# 03_MCU.net
KiCad netlist of a schematic drawn in Altium Designer
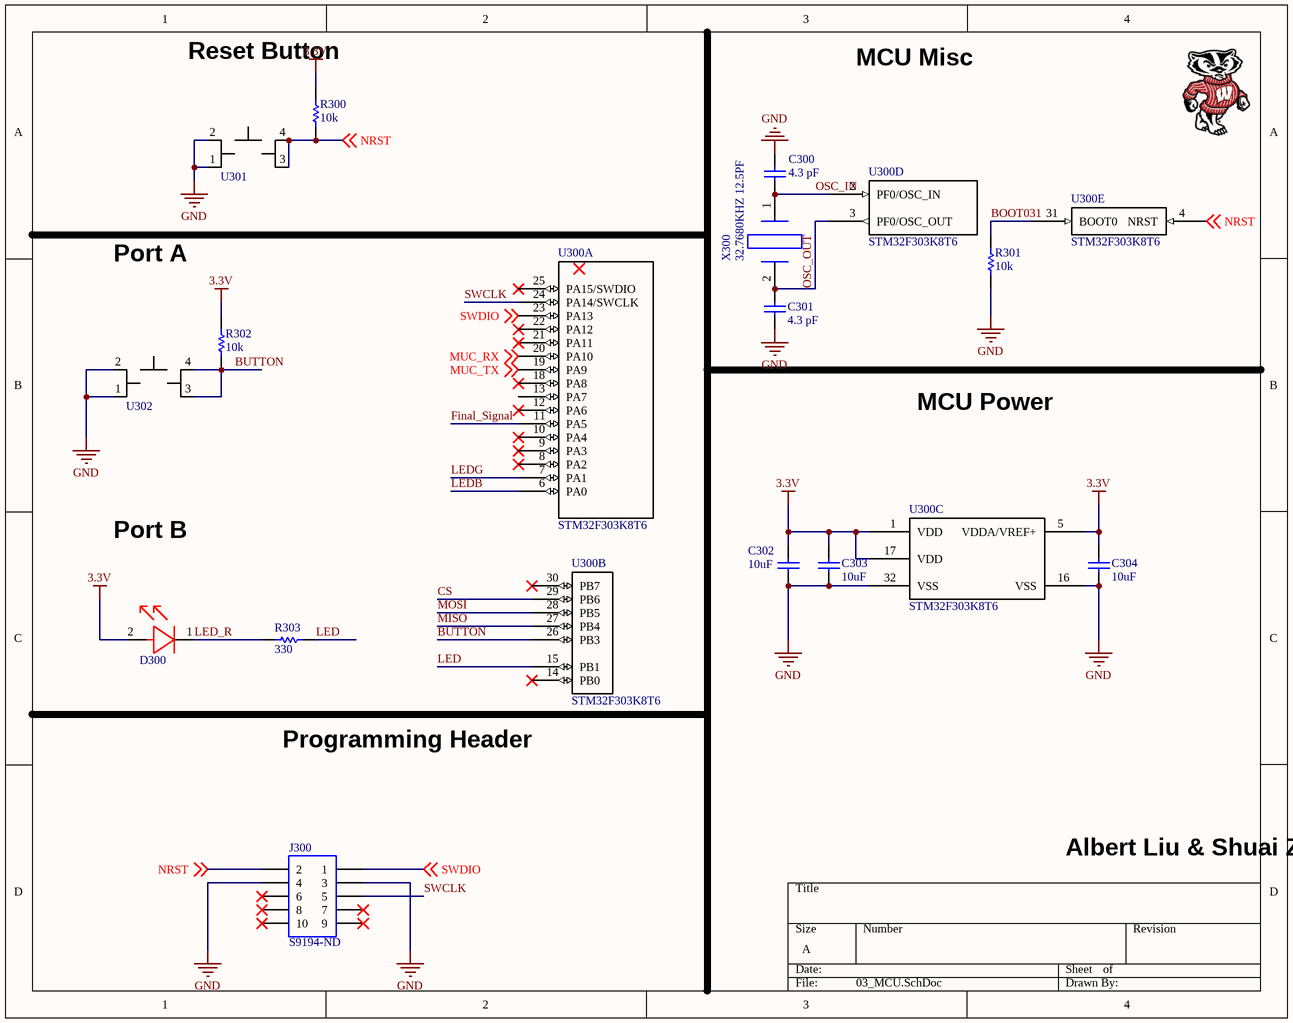
[diagram p0: 03_MCU.SchDoc]

(export (version "E")
  (design (tool "Eeschema 10.0.6"))
  (components
    (comp (ref "C300")
      (value "CAP_0805_P_004.30")
      (footprint "CAP_0805")
      (description "CAP CER 4.3PF 100V NP0 0805")
      (fields
        (field (name "MANUFACTURER") "Kyocera AVX")
        (field (name "MANUFACTURER PART NUMBER") "08051A4R3CAT2A")
        (field (name "CAPACITANCE VALUE") "4.3 pF")
      )
      (libsource (lib "ece315-S20") (part "CAP_0805_P_004.30"))
    )
    (comp (ref "C301")
      (value "CAP_0805_P_004.30")
      (footprint "CAP_0805")
      (description "CAP CER 4.3PF 100V NP0 0805")
      (fields
        (field (name "MANUFACTURER") "Kyocera AVX")
        (field (name "MANUFACTURER PART NUMBER") "08051A4R3CAT2A")
        (field (name "CAPACITANCE VALUE") "4.3 pF")
      )
      (libsource (lib "ece315-S20") (part "CAP_0805_P_004.30"))
    )
    (comp (ref "C302")
      (value "10uF")
      (footprint "CAP_0805")
      (description "CAP CER 10UF 16V X7R 0805")
      (fields
        (field (name "MANUFACTURER") "Samsung")
        (field (name "MANUFACTURER PART NUMBER") "CL21A106KPCLQNC")
        (field (name "CAPACITANCE") "10uF")
      )
      (libsource (lib "ece315-S20") (part "CAP_0805_U_010.00"))
    )
    (comp (ref "C303")
      (value "10uF")
      (footprint "CAP_0805")
      (description "CAP CER 10UF 16V X7R 0805")
      (fields
        (field (name "MANUFACTURER") "Samsung")
        (field (name "MANUFACTURER PART NUMBER") "CL21A106KPCLQNC")
        (field (name "CAPACITANCE") "10uF")
      )
      (libsource (lib "ece315-S20") (part "CAP_0805_U_010.00"))
    )
    (comp (ref "C304")
      (value "10uF")
      (footprint "CAP_0805")
      (description "CAP CER 10UF 16V X7R 0805")
      (fields
        (field (name "MANUFACTURER") "Samsung")
        (field (name "MANUFACTURER PART NUMBER") "CL21A106KPCLQNC")
        (field (name "CAPACITANCE") "10uF")
      )
      (libsource (lib "ece315-S20") (part "CAP_0805_U_010.00"))
    )
    (comp (ref "D300")
      (value "LED_RED_0805.1")
      (footprint "LED_RED_0805")
      (description "LED SUPER RED CLR THIN 0805 SMD")
      (fields
        (field (name "MANUFACTURER") "Vishay / Lite-On")
        (field (name "MANUFACTURER PART NUMBER") "LTST-C171KRKT")
      )
      (libsource (lib "ece315-S20") (part "LED_RED_0805.1"))
    )
    (comp (ref "J300")
      (value "SFH11-PBPC-D05-ST-BK")
      (footprint "SFH11-PBPC-D05-ST-BK")
      (description "CONN HDR 10POS 0.1 GOLD PCB")
      (fields (field (name "SUPPLIER PART NUMBER 1") "S9194-ND"))
      (libsource (lib "ece315-S20") (part "SFH11-PBPC-D05-ST-BK"))
    )
    (comp (ref "R300")
      (value "10K")
      (footprint "RES_0805")
      (description "RES SMD 10K OHM 1% 1/8W 0805")
      (fields
        (field (name "MANUFACTURER") "Panasonic / Panasonic ECG")
        (field (name "MANUFACTURER PART NUMBER") "ERJ-6ENF1002V")
        (field (name "RESISTANCE") "10k")
      )
      (libsource (lib "ece315-S20") (part "RES_0805_K_010.00"))
    )
    (comp (ref "R301")
      (value "10K")
      (footprint "RES_0805")
      (description "RES SMD 10K OHM 1% 1/8W 0805")
      (fields
        (field (name "MANUFACTURER") "Panasonic / Panasonic ECG")
        (field (name "MANUFACTURER PART NUMBER") "ERJ-6ENF1002V")
        (field (name "RESISTANCE") "10k")
      )
      (libsource (lib "ece315-S20") (part "RES_0805_K_010.00"))
    )
    (comp (ref "R302")
      (value "10K")
      (footprint "RES_0805")
      (description "RES SMD 10K OHM 1% 1/8W 0805")
      (fields
        (field (name "MANUFACTURER") "Panasonic / Panasonic ECG")
        (field (name "MANUFACTURER PART NUMBER") "ERJ-6ENF1002V")
        (field (name "RESISTANCE") "10k")
      )
      (libsource (lib "ece315-S20") (part "RES_0805_K_010.00"))
    )
    (comp (ref "R303")
      (value "330")
      (footprint "RES_0805")
      (description "RES SMD 330 OHM 1% 1/8W 0805")
      (fields
        (field (name "MANUFACTURER") "Panasonic / Panasonic ECG")
        (field (name "MANUFACTURER PART NUMBER") "ERJ-6ENF3300V")
        (field (name "RESISTANCE") "330")
      )
      (libsource (lib "ece315-S20") (part "RES_0805_R_330.00"))
    )
    (comp (ref "U300")
      (value "IC_STM32F303K8T6")
      (footprint "LQFP32")
      (description "ARM® Cortex®-M4 STM32 F3 Microcontroller IC 32-Bit 72MHz 64KB (64K x 8) FLASH 32-LQFP (7x7)")
      (fields
        (field (name "MANUFACTURER") "STMicroelectronics")
        (field (name "MANUFACTURER PART NUMBER") "STM32F303K8T6")
      )
      (libsource (lib "ece315-S20") (part "IC_STM32F303K8T6"))
    )
    (comp (ref "U301")
      (value "SWITCH_6mm_6mm_smd")
      (footprint "SWITCH_6mm_6mm_smd")
      (description "SWITCH TACTILE SPST-NO 0.05A 12V")
      (fields
        (field (name "MANUFACTURER") "C&K Components")
        (field (name "MANUFACTURER PART NUMBER") "PTS645SH50SMTR92 LFS")
      )
      (libsource (lib "ece315-S20") (part "SWITCH_6mm_6mm_smd"))
    )
    (comp (ref "U302")
      (value "SWITCH_6mm_6mm_smd")
      (footprint "SWITCH_6mm_6mm_smd")
      (description "SWITCH TACTILE SPST-NO 0.05A 12V")
      (fields
        (field (name "MANUFACTURER") "C&K Components")
        (field (name "MANUFACTURER PART NUMBER") "PTS645SH50SMTR92 LFS")
      )
      (libsource (lib "ece315-S20") (part "SWITCH_6mm_6mm_smd"))
    )
    (comp (ref "X300")
      (value "32.7680KHZ 12.5PF")
      (footprint "NX3215SA-32.768K-STD-MUA-8")
      (description "CRYSTAL 32.768KHZ 12.5PF SMD")
      (fields
        (field (name "MANUFACTURER") "Nihon Dempa Kogyo (NDK)")
        (field (name "MANUFACTURER PART NUMBER") "NX3215SA-32.768K-STD-MUA-8")
      )
      (libsource (lib "ece315-S20") (part "CRYSTAL_NX3215SA-32.768K"))
    )
  )
  (nets
    (net (code "1") (name "/BOOT031") (class "Default")
      (node (ref "R301") (pin "2") (pinfunction "2_2") (pintype "passive"))
      (node (ref "U300") (pin "31") (pinfunction "BOOT0_31") (pintype "input"))
    )
    (net (code "2") (name "/BUTTON") (class "Default")
      (node (ref "R302") (pin "1") (pinfunction "1_1") (pintype "passive"))
      (node (ref "U300") (pin "26") (pinfunction "PB3_26") (pintype "bidirectional"))
      (node (ref "U302") (pin "3") (pinfunction "3_3") (pintype "passive"))
      (node (ref "U302") (pin "4") (pinfunction "VCCIO_4") (pintype "passive"))
    )
    (net (code "3") (name "/CS") (class "Default")
      (node (ref "U300") (pin "29") (pinfunction "PB6_29") (pintype "bidirectional"))
    )
    (net (code "4") (name "/Final_Signal") (class "Default")
      (node (ref "U300") (pin "11") (pinfunction "PA5_11") (pintype "bidirectional"))
    )
    (net (code "5") (name "/LED") (class "Default")
      (node (ref "R303") (pin "2") (pinfunction "2_2") (pintype "passive"))
      (node (ref "U300") (pin "15") (pinfunction "PB1_15") (pintype "bidirectional"))
    )
    (net (code "6") (name "/LEDB") (class "Default")
      (node (ref "U300") (pin "6") (pinfunction "PA0_6") (pintype "bidirectional"))
    )
    (net (code "7") (name "/LEDG") (class "Default")
      (node (ref "U300") (pin "7") (pinfunction "PA1_7") (pintype "bidirectional"))
    )
    (net (code "8") (name "/LED_R") (class "Default")
      (node (ref "D300") (pin "1") (pinfunction "Cathode_1") (pintype "passive"))
      (node (ref "R303") (pin "1") (pinfunction "1_1") (pintype "passive"))
    )
    (net (code "9") (name "/MISO") (class "Default")
      (node (ref "U300") (pin "27") (pinfunction "PB4_27") (pintype "bidirectional"))
    )
    (net (code "10") (name "/MOSI") (class "Default")
      (node (ref "U300") (pin "28") (pinfunction "PB5_28") (pintype "bidirectional"))
    )
    (net (code "11") (name "/OSC_IN") (class "Default")
      (node (ref "C300") (pin "1") (pinfunction "1_1") (pintype "passive"))
      (node (ref "U300") (pin "2") (pinfunction "PF0/OSC_IN_2") (pintype "input"))
      (node (ref "X300") (pin "1") (pinfunction "1_1") (pintype "passive"))
    )
    (net (code "12") (name "/OSC_OUT") (class "Default")
      (node (ref "C301") (pin "2") (pinfunction "2_2") (pintype "passive"))
      (node (ref "U300") (pin "3") (pinfunction "PF0/OSC_OUT_3") (pintype "output"))
      (node (ref "X300") (pin "2") (pinfunction "2_2") (pintype "passive"))
    )
    (net (code "13") (name "/SWCLK") (class "Default")
      (node (ref "J300") (pin "5") (pinfunction "5_5") (pintype "passive"))
      (node (ref "U300") (pin "24") (pinfunction "PA14/SWCLK_24") (pintype "bidirectional"))
    )
    (net (code "14") (name "3.3V") (class "Default")
      (node (ref "C302") (pin "2") (pinfunction "2_2") (pintype "passive"))
      (node (ref "C303") (pin "2") (pinfunction "2_2") (pintype "passive"))
      (node (ref "C304") (pin "2") (pinfunction "2_2") (pintype "passive"))
      (node (ref "D300") (pin "2") (pinfunction "Anode_2") (pintype "passive"))
      (node (ref "R300") (pin "1") (pinfunction "1_1") (pintype "passive"))
      (node (ref "R302") (pin "2") (pinfunction "2_2") (pintype "passive"))
      (node (ref "U300") (pin "1") (pinfunction "VDD_1") (pintype "power_in"))
      (node (ref "U300") (pin "17") (pinfunction "VDD_17") (pintype "power_in"))
      (node (ref "U300") (pin "5") (pinfunction "VDDA/VREF+_5") (pintype "power_in"))
    )
    (net (code "15") (name "GND") (class "Default")
      (node (ref "C300") (pin "2") (pinfunction "2_2") (pintype "passive"))
      (node (ref "C301") (pin "1") (pinfunction "1_1") (pintype "passive"))
      (node (ref "C302") (pin "1") (pinfunction "1_1") (pintype "passive"))
      (node (ref "C303") (pin "1") (pinfunction "1_1") (pintype "passive"))
      (node (ref "C304") (pin "1") (pinfunction "1_1") (pintype "passive"))
      (node (ref "J300") (pin "3") (pinfunction "3_3") (pintype "passive"))
      (node (ref "J300") (pin "4") (pinfunction "4_4") (pintype "passive"))
      (node (ref "R301") (pin "1") (pinfunction "1_1") (pintype "passive"))
      (node (ref "U300") (pin "16") (pinfunction "VSS_16") (pintype "power_in"))
      (node (ref "U300") (pin "32") (pinfunction "VSS_32") (pintype "power_in"))
      (node (ref "U301") (pin "1") (pinfunction "1_1") (pintype "passive"))
      (node (ref "U301") (pin "2") (pinfunction "2_2") (pintype "passive"))
      (node (ref "U302") (pin "1") (pinfunction "1_1") (pintype "passive"))
      (node (ref "U302") (pin "2") (pinfunction "2_2") (pintype "passive"))
    )
    (net (code "16") (name "MUC_RX") (class "Default")
      (node (ref "U300") (pin "20") (pinfunction "PA10_20") (pintype "bidirectional"))
    )
    (net (code "17") (name "MUC_TX") (class "Default")
      (node (ref "U300") (pin "19") (pinfunction "PA9_19") (pintype "bidirectional"))
    )
    (net (code "18") (name "NRST") (class "Default")
      (node (ref "J300") (pin "2") (pinfunction "2_2") (pintype "passive"))
      (node (ref "R300") (pin "2") (pinfunction "2_2") (pintype "passive"))
      (node (ref "U300") (pin "4") (pinfunction "NRST_4") (pintype "input"))
      (node (ref "U301") (pin "3") (pinfunction "3_3") (pintype "passive"))
      (node (ref "U301") (pin "4") (pinfunction "VCCIO_4") (pintype "passive"))
    )
    (net (code "19") (name "SWDIO") (class "Default")
      (node (ref "J300") (pin "1") (pinfunction "1_1") (pintype "passive"))
      (node (ref "U300") (pin "23") (pinfunction "PA13_23") (pintype "bidirectional"))
    )
    (net (code "20") (name "unconnected-(J300-Pad6)") (class "Default")
      (node (ref "J300") (pin "6") (pinfunction "6_6") (pintype "passive+no_connect"))
    )
    (net (code "21") (name "unconnected-(J300-Pad7)") (class "Default")
      (node (ref "J300") (pin "7") (pinfunction "7_7") (pintype "passive+no_connect"))
    )
    (net (code "22") (name "unconnected-(J300-Pad8)") (class "Default")
      (node (ref "J300") (pin "8") (pinfunction "8_8") (pintype "passive+no_connect"))
    )
    (net (code "23") (name "unconnected-(J300-Pad9)") (class "Default")
      (node (ref "J300") (pin "9") (pinfunction "9_9") (pintype "passive+no_connect"))
    )
    (net (code "24") (name "unconnected-(J300-Pad10)") (class "Default")
      (node (ref "J300") (pin "10") (pinfunction "10_10") (pintype "passive+no_connect"))
    )
    (net (code "25") (name "unconnected-(U300A-PA2-Pad8)") (class "Default")
      (node (ref "U300") (pin "8") (pinfunction "PA2_8") (pintype "bidirectional+no_connect"))
    )
    (net (code "26") (name "unconnected-(U300A-PA3-Pad9)") (class "Default")
      (node (ref "U300") (pin "9") (pinfunction "PA3_9") (pintype "bidirectional+no_connect"))
    )
    (net (code "27") (name "unconnected-(U300A-PA4-Pad10)") (class "Default")
      (node (ref "U300") (pin "10") (pinfunction "PA4_10") (pintype "bidirectional+no_connect"))
    )
    (net (code "28") (name "unconnected-(U300A-PA6-Pad12)") (class "Default")
      (node (ref "U300") (pin "12") (pinfunction "PA6_12") (pintype "bidirectional+no_connect"))
    )
    (net (code "29") (name "unconnected-(U300A-PA7-Pad13)") (class "Default")
      (node (ref "U300") (pin "13") (pinfunction "PA7_13") (pintype "bidirectional"))
    )
    (net (code "30") (name "unconnected-(U300A-PA8-Pad18)") (class "Default")
      (node (ref "U300") (pin "18") (pinfunction "PA8_18") (pintype "bidirectional+no_connect"))
    )
    (net (code "31") (name "unconnected-(U300A-PA11-Pad21)") (class "Default")
      (node (ref "U300") (pin "21") (pinfunction "PA11_21") (pintype "bidirectional+no_connect"))
    )
    (net (code "32") (name "unconnected-(U300A-PA12-Pad22)") (class "Default")
      (node (ref "U300") (pin "22") (pinfunction "PA12_22") (pintype "bidirectional+no_connect"))
    )
    (net (code "33") (name "unconnected-(U300A-PA15{slash}SWDIO-Pad25)") (class "Default")
      (node (ref "U300") (pin "25") (pinfunction "PA15/SWDIO_25") (pintype "bidirectional+no_connect"))
    )
    (net (code "34") (name "unconnected-(U300B-PB0-Pad14)") (class "Default")
      (node (ref "U300") (pin "14") (pinfunction "PB0_14") (pintype "bidirectional+no_connect"))
    )
    (net (code "35") (name "unconnected-(U300B-PB7-Pad30)") (class "Default")
      (node (ref "U300") (pin "30") (pinfunction "PB7_30") (pintype "bidirectional+no_connect"))
    )
  )
)
